# usb_uart.net
KiCad netlist of a schematic drawn in EAGLE
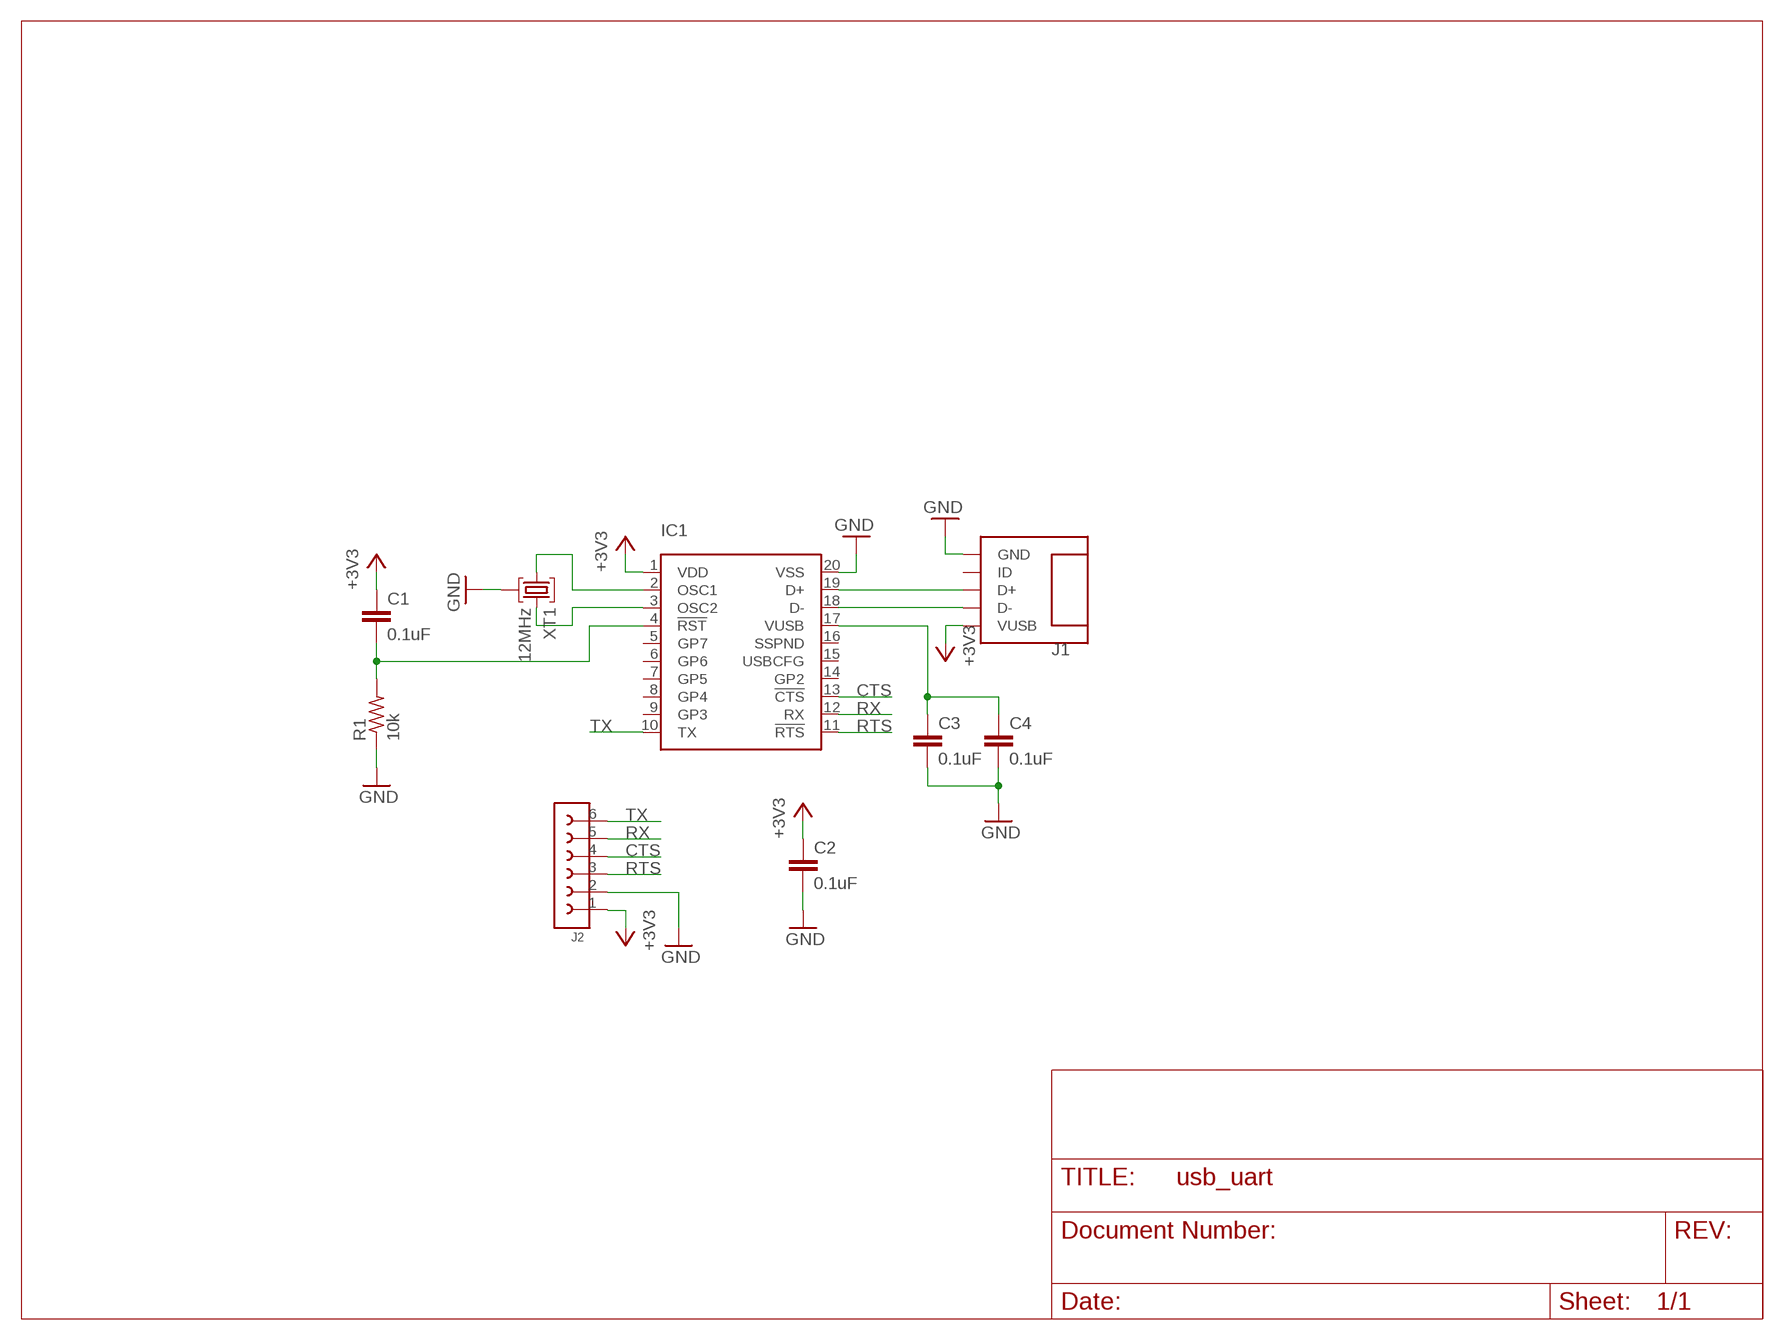
[diagram p0: schematic, sheet 1]

(export (version "E")
  (design (tool "Eeschema 10.0.6"))
  (components
    (comp (ref "C1")
      (value "0.1uF")
      (footprint "eagle-import:CAPC0603")
      (fields (field (name "MANUFACTURER") "KEMET"))
      (libsource (lib "eagle-import") (part "C?CVAC0603104Z3"))
    )
    (comp (ref "C2")
      (value "0.1uF")
      (footprint "eagle-import:CAPC0603")
      (fields (field (name "MANUFACTURER") "KEMET"))
      (libsource (lib "eagle-import") (part "C?CVAC0603104Z3"))
    )
    (comp (ref "C3")
      (value "0.1uF")
      (footprint "eagle-import:CAPC0603")
      (fields (field (name "MANUFACTURER") "KEMET"))
      (libsource (lib "eagle-import") (part "C?CVAC0603104Z3"))
    )
    (comp (ref "C4")
      (value "0.1uF")
      (footprint "eagle-import:CAPC0603")
      (fields (field (name "MANUFACTURER") "KEMET"))
      (libsource (lib "eagle-import") (part "C?CVAC0603104Z3"))
    )
    (comp (ref "IC1")
      (value "MCP2200-I/SS")
      (footprint "eagle-import:SOP65P775X200-20M")
      (libsource (lib "eagle-import") (part "MCP2200?-I/SS"))
    )
    (comp (ref "J1")
      (value "-1734035-1")
      (footprint "eagle-import:USB-MINIB-SMD+SMD+RET")
      (libsource (lib "eagle-import") (part "?-1734035-1"))
    )
    (comp (ref "J2")
      (value "61300611121")
      (footprint "eagle-import:PHSP254P1524X254X1154-6S")
      (fields (field (name "MANUFACTURER") "WURTH"))
      (libsource (lib "eagle-import") (part "6130061?1121"))
    )
    (comp (ref "R1")
      (value "10k")
      (footprint "eagle-import:RESC0603")
      (libsource (lib "eagle-import") (part "CRG?0603F10K10"))
    )
    (comp (ref "XT1")
      (value "12MHz")
      (footprint "eagle-import:CERAMIC740X340-3N")
      (fields (field (name "MANUFACTURER") "ABRACON"))
      (libsource (lib "eagle-import") (part "AWSCR-MGD-C12.00"))
    )
  )
  (nets
    (net (code "1") (name "+3V3") (class "Default")
      (node (ref "C1") (pin "1") (pinfunction "1_1") (pintype "passive"))
      (node (ref "C2") (pin "1") (pinfunction "1_1") (pintype "passive"))
      (node (ref "IC1") (pin "1") (pinfunction "VDD_1") (pintype "power_in"))
      (node (ref "J1") (pin "1") (pinfunction "VUSB_1") (pintype "bidirectional"))
      (node (ref "J2") (pin "1") (pinfunction "1_1") (pintype "passive"))
    )
    (net (code "2") (name "/CTS") (class "Default")
      (node (ref "IC1") (pin "13") (pinfunction "~{CTS}_13") (pintype "bidirectional"))
      (node (ref "J2") (pin "4") (pinfunction "4_4") (pintype "passive"))
    )
    (net (code "3") (name "/RTS") (class "Default")
      (node (ref "IC1") (pin "11") (pinfunction "~{RTS}_11") (pintype "bidirectional"))
      (node (ref "J2") (pin "3") (pinfunction "3_3") (pintype "passive"))
    )
    (net (code "4") (name "/RX") (class "Default")
      (node (ref "IC1") (pin "12") (pinfunction "RX_12") (pintype "bidirectional"))
      (node (ref "J2") (pin "5") (pinfunction "5_5") (pintype "passive"))
    )
    (net (code "5") (name "/TX") (class "Default")
      (node (ref "IC1") (pin "10") (pinfunction "TX_10") (pintype "bidirectional"))
      (node (ref "J2") (pin "6") (pinfunction "6_6") (pintype "passive"))
    )
    (net (code "6") (name "GND") (class "Default")
      (node (ref "C2") (pin "2") (pinfunction "2_2") (pintype "passive"))
      (node (ref "C3") (pin "2") (pinfunction "2_2") (pintype "passive"))
      (node (ref "C4") (pin "2") (pinfunction "2_2") (pintype "passive"))
      (node (ref "IC1") (pin "20") (pinfunction "VSS_20") (pintype "power_in"))
      (node (ref "J1") (pin "5") (pinfunction "GND_5") (pintype "bidirectional"))
      (node (ref "J2") (pin "2") (pinfunction "2_2") (pintype "passive"))
      (node (ref "R1") (pin "P$1") (pinfunction "1_P$1") (pintype "passive"))
      (node (ref "XT1") (pin "2") (pinfunction "2_2") (pintype "passive"))
    )
    (net (code "7") (name "Net-(IC1-D+)") (class "Default")
      (node (ref "IC1") (pin "19") (pinfunction "D+_19") (pintype "bidirectional"))
      (node (ref "J1") (pin "3") (pinfunction "D+_3") (pintype "bidirectional"))
    )
    (net (code "8") (name "Net-(IC1-D-)") (class "Default")
      (node (ref "IC1") (pin "18") (pinfunction "D-_18") (pintype "bidirectional"))
      (node (ref "J1") (pin "2") (pinfunction "D-_2") (pintype "bidirectional"))
    )
    (net (code "9") (name "Net-(IC1-OSC1)") (class "Default")
      (node (ref "IC1") (pin "2") (pinfunction "OSC1_2") (pintype "bidirectional"))
      (node (ref "XT1") (pin "1") (pinfunction "1_1") (pintype "passive"))
    )
    (net (code "10") (name "Net-(IC1-OSC2)") (class "Default")
      (node (ref "IC1") (pin "3") (pinfunction "OSC2_3") (pintype "bidirectional"))
      (node (ref "XT1") (pin "3") (pinfunction "3_3") (pintype "passive"))
    )
    (net (code "11") (name "Net-(IC1-VUSB)") (class "Default")
      (node (ref "C3") (pin "1") (pinfunction "1_1") (pintype "passive"))
      (node (ref "C4") (pin "1") (pinfunction "1_1") (pintype "passive"))
      (node (ref "IC1") (pin "17") (pinfunction "VUSB_17") (pintype "bidirectional"))
    )
    (net (code "12") (name "Net-(IC1-~{RST})") (class "Default")
      (node (ref "C1") (pin "2") (pinfunction "2_2") (pintype "passive"))
      (node (ref "IC1") (pin "4") (pinfunction "~{RST}_4") (pintype "bidirectional"))
      (node (ref "R1") (pin "P$2") (pinfunction "2_P$2") (pintype "passive"))
    )
    (net (code "13") (name "unconnected-(IC1-GP2-Pad14)") (class "Default")
      (node (ref "IC1") (pin "14") (pinfunction "GP2_14") (pintype "bidirectional"))
    )
    (net (code "14") (name "unconnected-(IC1-GP3-Pad9)") (class "Default")
      (node (ref "IC1") (pin "9") (pinfunction "GP3_9") (pintype "bidirectional"))
    )
    (net (code "15") (name "unconnected-(IC1-GP4-Pad8)") (class "Default")
      (node (ref "IC1") (pin "8") (pinfunction "GP4_8") (pintype "bidirectional"))
    )
    (net (code "16") (name "unconnected-(IC1-GP5-Pad7)") (class "Default")
      (node (ref "IC1") (pin "7") (pinfunction "GP5_7") (pintype "bidirectional"))
    )
    (net (code "17") (name "unconnected-(IC1-GP6-Pad6)") (class "Default")
      (node (ref "IC1") (pin "6") (pinfunction "GP6_6") (pintype "bidirectional"))
    )
    (net (code "18") (name "unconnected-(IC1-GP7-Pad5)") (class "Default")
      (node (ref "IC1") (pin "5") (pinfunction "GP7_5") (pintype "bidirectional"))
    )
    (net (code "19") (name "unconnected-(IC1-SSPND-Pad16)") (class "Default")
      (node (ref "IC1") (pin "16") (pinfunction "SSPND_16") (pintype "bidirectional"))
    )
    (net (code "20") (name "unconnected-(IC1-USBCFG-Pad15)") (class "Default")
      (node (ref "IC1") (pin "15") (pinfunction "USBCFG_15") (pintype "bidirectional"))
    )
    (net (code "21") (name "unconnected-(J1-ID-Pad4)") (class "Default")
      (node (ref "J1") (pin "4") (pinfunction "ID_4") (pintype "bidirectional"))
    )
  )
)
